# R303X.net
KiCad netlist of a schematic drawn in EAGLE
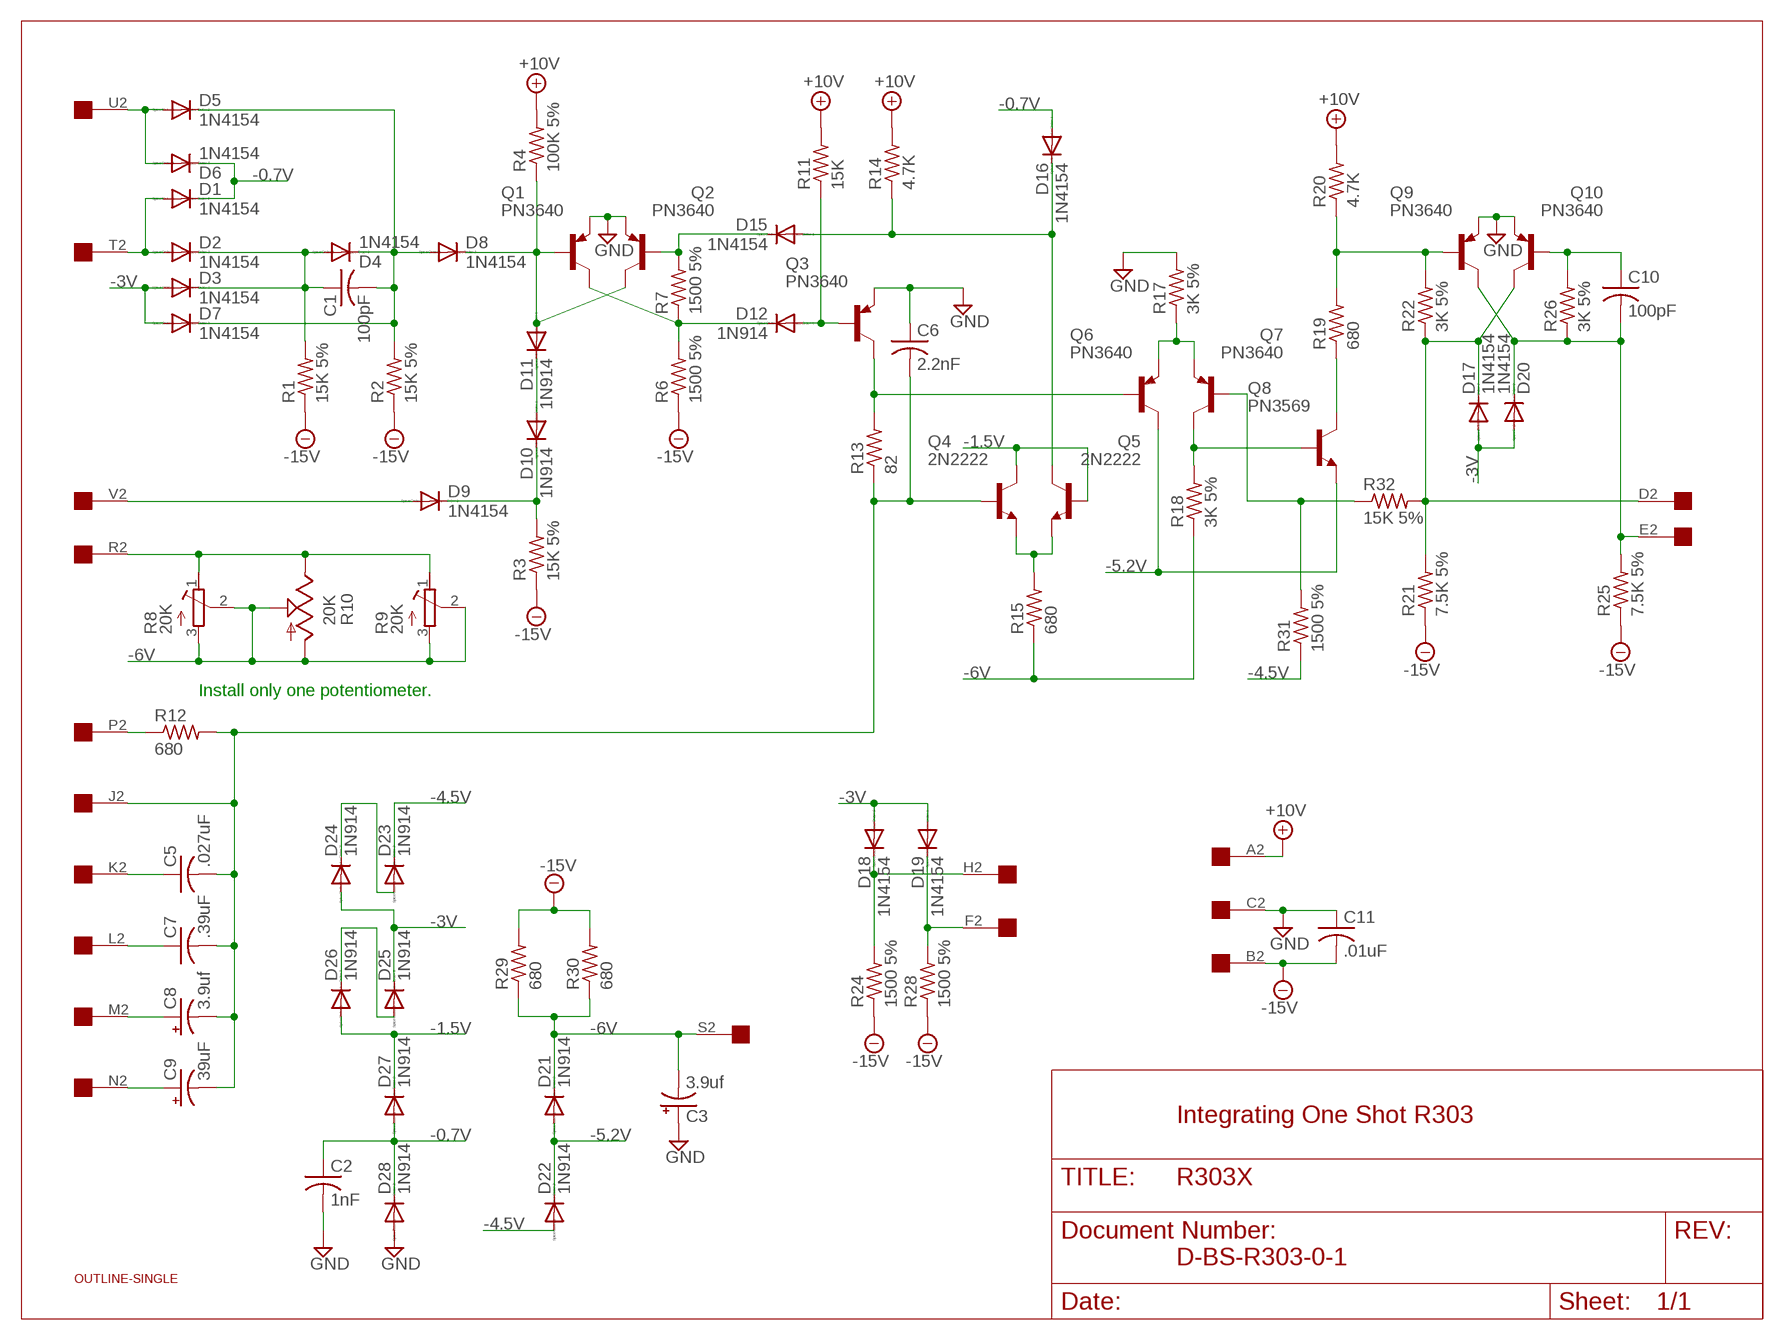
[diagram p0: schematic, sheet 1]

(export (version "E")
  (design (tool "Eeschema 10.0.6"))
  (components
    (comp (ref "C1")
      (value "100pF")
      (footprint "eagle-import:C075-032X103")
      (libsource (lib "eagle-import") (part "C-US075-032X103"))
    )
    (comp (ref "C2")
      (value "1nF")
      (footprint "eagle-import:C050-025X075")
      (libsource (lib "eagle-import") (part "C-US050-025X075"))
    )
    (comp (ref "C3")
      (value "3.9uf")
      (footprint "eagle-import:E12-4")
      (libsource (lib "eagle-import") (part "CPOL-USE12-4AXIAL"))
    )
    (comp (ref "C5")
      (value ".027uF")
      (footprint "eagle-import:C225-062X268")
      (libsource (lib "eagle-import") (part "C-US225-062X268"))
    )
    (comp (ref "C6")
      (value "2.2nF")
      (footprint "eagle-import:C050-025X075")
      (libsource (lib "eagle-import") (part "C-US050-025X075"))
    )
    (comp (ref "C7")
      (value ".39uF")
      (footprint "eagle-import:C325-137X374")
      (libsource (lib "eagle-import") (part "C-US325-137X374"))
    )
    (comp (ref "C8")
      (value "3.9uf")
      (footprint "eagle-import:E12-4")
      (libsource (lib "eagle-import") (part "CPOL-USE12-4AXIAL"))
    )
    (comp (ref "C9")
      (value "39uF")
      (footprint "eagle-import:E15-5")
      (libsource (lib "eagle-import") (part "CPOL-USE15-5AXIAL"))
    )
    (comp (ref "C10")
      (value "100pF")
      (footprint "eagle-import:C075-032X103")
      (libsource (lib "eagle-import") (part "C-US075-032X103"))
    )
    (comp (ref "C11")
      (value ".01uF")
      (footprint "eagle-import:C075-032X103")
      (libsource (lib "eagle-import") (part "C-US075-032X103"))
    )
    (comp (ref "D1")
      (value "1N4154")
      (footprint "eagle-import:DO35-10")
      (libsource (lib "eagle-import") (part "1N4148DO35-10"))
    )
    (comp (ref "D2")
      (value "1N4154")
      (footprint "eagle-import:DO35-10")
      (libsource (lib "eagle-import") (part "1N4148DO35-10"))
    )
    (comp (ref "D3")
      (value "1N4154")
      (footprint "eagle-import:DO35-10")
      (libsource (lib "eagle-import") (part "1N4148DO35-10"))
    )
    (comp (ref "D4")
      (value "1N4154")
      (footprint "eagle-import:DO35-10")
      (libsource (lib "eagle-import") (part "1N4148DO35-10"))
    )
    (comp (ref "D5")
      (value "1N4154")
      (footprint "eagle-import:DO35-10")
      (libsource (lib "eagle-import") (part "1N4148DO35-10"))
    )
    (comp (ref "D6")
      (value "1N4154")
      (footprint "eagle-import:DO35-10")
      (libsource (lib "eagle-import") (part "1N4148DO35-10"))
    )
    (comp (ref "D7")
      (value "1N4154")
      (footprint "eagle-import:DO35-10")
      (libsource (lib "eagle-import") (part "1N4148DO35-10"))
    )
    (comp (ref "D8")
      (value "1N4154")
      (footprint "eagle-import:DO35-10")
      (libsource (lib "eagle-import") (part "1N4148DO35-10"))
    )
    (comp (ref "D9")
      (value "1N4154")
      (footprint "eagle-import:DO35-10")
      (libsource (lib "eagle-import") (part "1N4148DO35-10"))
    )
    (comp (ref "D10")
      (value "1N914")
      (footprint "eagle-import:DO35-10")
      (libsource (lib "eagle-import") (part "1N4148DO35-10"))
    )
    (comp (ref "D11")
      (value "1N914")
      (footprint "eagle-import:DO35-10")
      (libsource (lib "eagle-import") (part "1N4148DO35-10"))
    )
    (comp (ref "D12")
      (value "1N914")
      (footprint "eagle-import:DO35-10")
      (libsource (lib "eagle-import") (part "1N4148DO35-10"))
    )
    (comp (ref "D15")
      (value "1N4154")
      (footprint "eagle-import:DO35-10")
      (libsource (lib "eagle-import") (part "1N4148DO35-10"))
    )
    (comp (ref "D16")
      (value "1N4154")
      (footprint "eagle-import:DO35-10")
      (libsource (lib "eagle-import") (part "1N4148DO35-10"))
    )
    (comp (ref "D17")
      (value "1N4154")
      (footprint "eagle-import:DO35-10")
      (libsource (lib "eagle-import") (part "1N4148DO35-10"))
    )
    (comp (ref "D18")
      (value "1N4154")
      (footprint "eagle-import:DO35-10")
      (libsource (lib "eagle-import") (part "1N4148DO35-10"))
    )
    (comp (ref "D19")
      (value "1N4154")
      (footprint "eagle-import:DO35-10")
      (libsource (lib "eagle-import") (part "1N4148DO35-10"))
    )
    (comp (ref "D20")
      (value "1N4154")
      (footprint "eagle-import:DO35-10")
      (libsource (lib "eagle-import") (part "1N4148DO35-10"))
    )
    (comp (ref "D21")
      (value "1N914")
      (footprint "eagle-import:DO35-10")
      (libsource (lib "eagle-import") (part "1N4148DO35-10"))
    )
    (comp (ref "D22")
      (value "1N914")
      (footprint "eagle-import:DO35-10")
      (libsource (lib "eagle-import") (part "1N4148DO35-10"))
    )
    (comp (ref "D23")
      (value "1N914")
      (footprint "eagle-import:DO35-10")
      (libsource (lib "eagle-import") (part "1N4148DO35-10"))
    )
    (comp (ref "D24")
      (value "1N914")
      (footprint "eagle-import:DO35-10")
      (libsource (lib "eagle-import") (part "1N4148DO35-10"))
    )
    (comp (ref "D25")
      (value "1N914")
      (footprint "eagle-import:DO35-10")
      (libsource (lib "eagle-import") (part "1N4148DO35-10"))
    )
    (comp (ref "D26")
      (value "1N914")
      (footprint "eagle-import:DO35-10")
      (libsource (lib "eagle-import") (part "1N4148DO35-10"))
    )
    (comp (ref "D27")
      (value "1N914")
      (footprint "eagle-import:DO35-10")
      (libsource (lib "eagle-import") (part "1N4148DO35-10"))
    )
    (comp (ref "D28")
      (value "1N914")
      (footprint "eagle-import:DO35-10")
      (libsource (lib "eagle-import") (part "1N4148DO35-10"))
    )
    (comp (ref "Q1")
      (value "PN3640")
      (footprint "eagle-import:TO39")
      (libsource (lib "eagle-import") (part "2N2904"))
    )
    (comp (ref "Q2")
      (value "PN3640")
      (footprint "eagle-import:TO39")
      (libsource (lib "eagle-import") (part "2N2904"))
    )
    (comp (ref "Q3")
      (value "PN3640")
      (footprint "eagle-import:TO39")
      (libsource (lib "eagle-import") (part "2N2904"))
    )
    (comp (ref "Q4")
      (value "2N2222")
      (footprint "eagle-import:TO5")
      (libsource (lib "eagle-import") (part "2N2102"))
    )
    (comp (ref "Q5")
      (value "2N2222")
      (footprint "eagle-import:TO5")
      (libsource (lib "eagle-import") (part "2N2102"))
    )
    (comp (ref "Q6")
      (value "PN3640")
      (footprint "eagle-import:TO39")
      (libsource (lib "eagle-import") (part "2N2904"))
    )
    (comp (ref "Q7")
      (value "PN3640")
      (footprint "eagle-import:TO39")
      (libsource (lib "eagle-import") (part "2N2904"))
    )
    (comp (ref "Q8")
      (value "PN3569")
      (footprint "eagle-import:TO5")
      (libsource (lib "eagle-import") (part "2N2102"))
    )
    (comp (ref "Q9")
      (value "PN3640")
      (footprint "eagle-import:TO39")
      (libsource (lib "eagle-import") (part "2N2904"))
    )
    (comp (ref "Q10")
      (value "PN3640")
      (footprint "eagle-import:TO39")
      (libsource (lib "eagle-import") (part "2N2904"))
    )
    (comp (ref "R1")
      (value "15K 5%")
      (footprint "eagle-import:0207_10")
      (libsource (lib "eagle-import") (part "R-US_0207/10"))
    )
    (comp (ref "R2")
      (value "15K 5%")
      (footprint "eagle-import:0207_10")
      (libsource (lib "eagle-import") (part "R-US_0207/10"))
    )
    (comp (ref "R3")
      (value "15K 5%")
      (footprint "eagle-import:0207_10")
      (libsource (lib "eagle-import") (part "R-US_0207/10"))
    )
    (comp (ref "R4")
      (value "100K 5%")
      (footprint "eagle-import:0207_10")
      (libsource (lib "eagle-import") (part "R-US_0207/10"))
    )
    (comp (ref "R6")
      (value "1500 5%")
      (footprint "eagle-import:0207_10")
      (libsource (lib "eagle-import") (part "R-US_0207/10"))
    )
    (comp (ref "R7")
      (value "1500 5%")
      (footprint "eagle-import:0207_10")
      (libsource (lib "eagle-import") (part "R-US_0207/10"))
    )
    (comp (ref "R8")
      (value "20K")
      (footprint "eagle-import:RTRIM43P")
      (libsource (lib "eagle-import") (part "R-TRIMM43P"))
    )
    (comp (ref "R9")
      (value "20K")
      (footprint "eagle-import:3006Y")
      (libsource (lib "eagle-import") (part "275P"))
    )
    (comp (ref "R10")
      (value "20K")
      (footprint "eagle-import:B25P")
      (libsource (lib "eagle-import") (part "TRIM_US-B25P"))
    )
    (comp (ref "R11")
      (value "15K")
      (footprint "eagle-import:0207_10")
      (libsource (lib "eagle-import") (part "R-US_0207/10"))
    )
    (comp (ref "R12")
      (value "680")
      (footprint "eagle-import:0207_10")
      (libsource (lib "eagle-import") (part "R-US_0207/10"))
    )
    (comp (ref "R13")
      (value "82")
      (footprint "eagle-import:0207_10")
      (libsource (lib "eagle-import") (part "R-US_0207/10"))
    )
    (comp (ref "R14")
      (value "4.7K")
      (footprint "eagle-import:0207_10")
      (libsource (lib "eagle-import") (part "R-US_0207/10"))
    )
    (comp (ref "R15")
      (value "680")
      (footprint "eagle-import:0207_10")
      (libsource (lib "eagle-import") (part "R-US_0207/10"))
    )
    (comp (ref "R17")
      (value "3K 5%")
      (footprint "eagle-import:0207_10")
      (libsource (lib "eagle-import") (part "R-US_0207/10"))
    )
    (comp (ref "R18")
      (value "3K 5%")
      (footprint "eagle-import:0207_10")
      (libsource (lib "eagle-import") (part "R-US_0207/10"))
    )
    (comp (ref "R19")
      (value "680")
      (footprint "eagle-import:0207_10")
      (libsource (lib "eagle-import") (part "R-US_0207/10"))
    )
    (comp (ref "R20")
      (value "4.7K")
      (footprint "eagle-import:0207_10")
      (libsource (lib "eagle-import") (part "R-US_0207/10"))
    )
    (comp (ref "R21")
      (value "7.5K 5%")
      (footprint "eagle-import:0207_10")
      (libsource (lib "eagle-import") (part "R-US_0207/10"))
    )
    (comp (ref "R22")
      (value "3K 5%")
      (footprint "eagle-import:0207_10")
      (libsource (lib "eagle-import") (part "R-US_0207/10"))
    )
    (comp (ref "R24")
      (value "1500 5%")
      (footprint "eagle-import:0207_10")
      (libsource (lib "eagle-import") (part "R-US_0207/10"))
    )
    (comp (ref "R25")
      (value "7.5K 5%")
      (footprint "eagle-import:0207_10")
      (libsource (lib "eagle-import") (part "R-US_0207/10"))
    )
    (comp (ref "R26")
      (value "3K 5%")
      (footprint "eagle-import:0207_10")
      (libsource (lib "eagle-import") (part "R-US_0207/10"))
    )
    (comp (ref "R28")
      (value "1500 5%")
      (footprint "eagle-import:0207_10")
      (libsource (lib "eagle-import") (part "R-US_0207/10"))
    )
    (comp (ref "R29")
      (value "680")
      (footprint "eagle-import:0207_10")
      (libsource (lib "eagle-import") (part "R-US_0207/10"))
    )
    (comp (ref "R30")
      (value "680")
      (footprint "eagle-import:0207_10")
      (libsource (lib "eagle-import") (part "R-US_0207/10"))
    )
    (comp (ref "R31")
      (value "1500 5%")
      (footprint "eagle-import:0207_10")
      (libsource (lib "eagle-import") (part "R-US_0207/10"))
    )
    (comp (ref "R32")
      (value "15K 5%")
      (footprint "eagle-import:0207_10")
      (libsource (lib "eagle-import") (part "R-US_0207/10"))
    )
    (comp (ref "U$1")
      (value "OUTLINE-SINGLE")
      (footprint "eagle-import:SINGLE")
      (libsource (lib "eagle-import") (part "OUTLINE-SINGLE"))
    )
    (comp (ref "U$2")
      (value "EDGE-1")
      (footprint "eagle-import:EDGE-CON1")
      (libsource (lib "eagle-import") (part "EDGE-1"))
    )
  )
  (nets
    (net (code "1") (name "+10V") (class "Default")
      (node (ref "R11") (pin "2") (pinfunction "2_2") (pintype "passive"))
      (node (ref "R14") (pin "2") (pinfunction "2_2") (pintype "passive"))
      (node (ref "R20") (pin "2") (pinfunction "2_2") (pintype "passive"))
      (node (ref "R4") (pin "2") (pinfunction "2_2") (pintype "passive"))
      (node (ref "U$2") (pin "A2") (pinfunction "1_A2") (pintype "bidirectional"))
    )
    (net (code "2") (name "-15V") (class "Default")
      (node (ref "C11") (pin "2") (pinfunction "2_2") (pintype "passive"))
      (node (ref "R1") (pin "1") (pinfunction "1_1") (pintype "passive"))
      (node (ref "R2") (pin "1") (pinfunction "1_1") (pintype "passive"))
      (node (ref "R21") (pin "1") (pinfunction "1_1") (pintype "passive"))
      (node (ref "R24") (pin "1") (pinfunction "1_1") (pintype "passive"))
      (node (ref "R25") (pin "1") (pinfunction "1_1") (pintype "passive"))
      (node (ref "R28") (pin "1") (pinfunction "1_1") (pintype "passive"))
      (node (ref "R29") (pin "2") (pinfunction "2_2") (pintype "passive"))
      (node (ref "R3") (pin "1") (pinfunction "1_1") (pintype "passive"))
      (node (ref "R30") (pin "2") (pinfunction "2_2") (pintype "passive"))
      (node (ref "R6") (pin "1") (pinfunction "1_1") (pintype "passive"))
      (node (ref "U$2") (pin "B2") (pinfunction "1_B2") (pintype "bidirectional"))
    )
    (net (code "3") (name "/-0.7V") (class "Default")
      (node (ref "C2") (pin "1") (pinfunction "1_1") (pintype "passive"))
      (node (ref "D1") (pin "C") (pinfunction "C_C") (pintype "passive"))
      (node (ref "D16") (pin "A") (pinfunction "A_A") (pintype "passive"))
      (node (ref "D27") (pin "A") (pinfunction "A_A") (pintype "passive"))
      (node (ref "D28") (pin "C") (pinfunction "C_C") (pintype "passive"))
      (node (ref "D6") (pin "C") (pinfunction "C_C") (pintype "passive"))
    )
    (net (code "4") (name "/-1.5V") (class "Default")
      (node (ref "D26") (pin "A") (pinfunction "A_A") (pintype "passive"))
      (node (ref "D27") (pin "C") (pinfunction "C_C") (pintype "passive"))
      (node (ref "Q4") (pin "3") (pinfunction "C_3") (pintype "passive"))
      (node (ref "Q5") (pin "2") (pinfunction "B_2") (pintype "passive"))
    )
    (net (code "5") (name "/-3V") (class "Default")
      (node (ref "D17") (pin "A") (pinfunction "A_A") (pintype "passive"))
      (node (ref "D18") (pin "A") (pinfunction "A_A") (pintype "passive"))
      (node (ref "D19") (pin "A") (pinfunction "A_A") (pintype "passive"))
      (node (ref "D20") (pin "A") (pinfunction "A_A") (pintype "passive"))
      (node (ref "D24") (pin "A") (pinfunction "A_A") (pintype "passive"))
      (node (ref "D25") (pin "C") (pinfunction "C_C") (pintype "passive"))
      (node (ref "D3") (pin "A") (pinfunction "A_A") (pintype "passive"))
      (node (ref "D7") (pin "A") (pinfunction "A_A") (pintype "passive"))
    )
    (net (code "6") (name "/-4.5V") (class "Default")
      (node (ref "D22") (pin "A") (pinfunction "A_A") (pintype "passive"))
      (node (ref "D23") (pin "C") (pinfunction "C_C") (pintype "passive"))
      (node (ref "R31") (pin "1") (pinfunction "1_1") (pintype "passive"))
    )
    (net (code "7") (name "/-5.2V") (class "Default")
      (node (ref "D21") (pin "A") (pinfunction "A_A") (pintype "passive"))
      (node (ref "D22") (pin "C") (pinfunction "C_C") (pintype "passive"))
      (node (ref "Q6") (pin "3") (pinfunction "C_3") (pintype "passive"))
      (node (ref "Q8") (pin "1") (pinfunction "E_1") (pintype "passive"))
    )
    (net (code "8") (name "/-6V") (class "Default")
      (node (ref "C3") (pin "-") (pinfunction "-_-") (pintype "passive"))
      (node (ref "D21") (pin "C") (pinfunction "C_C") (pintype "passive"))
      (node (ref "R10") (pin "A") (pinfunction "A_A") (pintype "passive"))
      (node (ref "R10") (pin "S") (pinfunction "S_S") (pintype "passive"))
      (node (ref "R15") (pin "1") (pinfunction "1_1") (pintype "passive"))
      (node (ref "R18") (pin "1") (pinfunction "1_1") (pintype "passive"))
      (node (ref "R29") (pin "1") (pinfunction "1_1") (pintype "passive"))
      (node (ref "R30") (pin "1") (pinfunction "1_1") (pintype "passive"))
      (node (ref "R8") (pin "2") (pinfunction "S_2") (pintype "passive"))
      (node (ref "R8") (pin "3") (pinfunction "A_3") (pintype "passive"))
      (node (ref "R9") (pin "2") (pinfunction "S_2") (pintype "passive"))
      (node (ref "R9") (pin "3") (pinfunction "E_3") (pintype "passive"))
      (node (ref "U$2") (pin "S2") (pinfunction "1_S2") (pintype "bidirectional"))
    )
    (net (code "9") (name "GND") (class "Default")
      (node (ref "C11") (pin "1") (pinfunction "1_1") (pintype "passive"))
      (node (ref "C2") (pin "2") (pinfunction "2_2") (pintype "passive"))
      (node (ref "C3") (pin "+") (pinfunction "+_+") (pintype "passive"))
      (node (ref "C6") (pin "1") (pinfunction "1_1") (pintype "passive"))
      (node (ref "D28") (pin "A") (pinfunction "A_A") (pintype "passive"))
      (node (ref "Q1") (pin "1") (pinfunction "E_1") (pintype "passive"))
      (node (ref "Q10") (pin "1") (pinfunction "E_1") (pintype "passive"))
      (node (ref "Q2") (pin "1") (pinfunction "E_1") (pintype "passive"))
      (node (ref "Q3") (pin "1") (pinfunction "E_1") (pintype "passive"))
      (node (ref "Q9") (pin "1") (pinfunction "E_1") (pintype "passive"))
      (node (ref "R17") (pin "2") (pinfunction "2_2") (pintype "passive"))
      (node (ref "U$2") (pin "C2") (pinfunction "1_C2") (pintype "bidirectional"))
    )
    (net (code "10") (name "Net-(C1-Pad1)") (class "Default")
      (node (ref "C1") (pin "1") (pinfunction "1_1") (pintype "passive"))
      (node (ref "D2") (pin "C") (pinfunction "C_C") (pintype "passive"))
      (node (ref "D3") (pin "C") (pinfunction "C_C") (pintype "passive"))
      (node (ref "D4") (pin "A") (pinfunction "A_A") (pintype "passive"))
      (node (ref "R1") (pin "2") (pinfunction "2_2") (pintype "passive"))
    )
    (net (code "11") (name "Net-(C1-Pad2)") (class "Default")
      (node (ref "C1") (pin "2") (pinfunction "2_2") (pintype "passive"))
      (node (ref "D4") (pin "C") (pinfunction "C_C") (pintype "passive"))
      (node (ref "D5") (pin "C") (pinfunction "C_C") (pintype "passive"))
      (node (ref "D7") (pin "C") (pinfunction "C_C") (pintype "passive"))
      (node (ref "D8") (pin "A") (pinfunction "A_A") (pintype "passive"))
      (node (ref "R2") (pin "2") (pinfunction "2_2") (pintype "passive"))
    )
    (net (code "12") (name "Net-(D10-PadA)") (class "Default")
      (node (ref "D10") (pin "A") (pinfunction "A_A") (pintype "passive"))
      (node (ref "D11") (pin "C") (pinfunction "C_C") (pintype "passive"))
    )
    (net (code "13") (name "Net-(D10-PadC)") (class "Default")
      (node (ref "D10") (pin "C") (pinfunction "C_C") (pintype "passive"))
      (node (ref "D9") (pin "C") (pinfunction "C_C") (pintype "passive"))
      (node (ref "R3") (pin "2") (pinfunction "2_2") (pintype "passive"))
    )
    (net (code "14") (name "Net-(D23-PadA)") (class "Default")
      (node (ref "D23") (pin "A") (pinfunction "A_A") (pintype "passive"))
      (node (ref "D24") (pin "C") (pinfunction "C_C") (pintype "passive"))
    )
    (net (code "15") (name "Net-(D25-PadA)") (class "Default")
      (node (ref "D25") (pin "A") (pinfunction "A_A") (pintype "passive"))
      (node (ref "D26") (pin "C") (pinfunction "C_C") (pintype "passive"))
    )
    (net (code "16") (name "Net-(Q1-B)") (class "Default")
      (node (ref "D11") (pin "A") (pinfunction "A_A") (pintype "passive"))
      (node (ref "D8") (pin "C") (pinfunction "C_C") (pintype "passive"))
      (node (ref "Q1") (pin "2") (pinfunction "B_2") (pintype "passive"))
      (node (ref "Q2") (pin "3") (pinfunction "C_3") (pintype "passive"))
      (node (ref "R4") (pin "1") (pinfunction "1_1") (pintype "passive"))
    )
    (net (code "17") (name "Net-(Q1-C)") (class "Default")
      (node (ref "D12") (pin "C") (pinfunction "C_C") (pintype "passive"))
      (node (ref "Q1") (pin "3") (pinfunction "C_3") (pintype "passive"))
      (node (ref "R6") (pin "2") (pinfunction "2_2") (pintype "passive"))
      (node (ref "R7") (pin "1") (pinfunction "1_1") (pintype "passive"))
    )
    (net (code "18") (name "Net-(Q2-B)") (class "Default")
      (node (ref "D15") (pin "C") (pinfunction "C_C") (pintype "passive"))
      (node (ref "Q2") (pin "2") (pinfunction "B_2") (pintype "passive"))
      (node (ref "R7") (pin "2") (pinfunction "2_2") (pintype "passive"))
    )
    (net (code "19") (name "Net-(Q3-B)") (class "Default")
      (node (ref "D12") (pin "A") (pinfunction "A_A") (pintype "passive"))
      (node (ref "Q3") (pin "2") (pinfunction "B_2") (pintype "passive"))
      (node (ref "R11") (pin "1") (pinfunction "1_1") (pintype "passive"))
    )
    (net (code "20") (name "Net-(Q3-C)") (class "Default")
      (node (ref "Q3") (pin "3") (pinfunction "C_3") (pintype "passive"))
      (node (ref "Q6") (pin "2") (pinfunction "B_2") (pintype "passive"))
      (node (ref "R13") (pin "2") (pinfunction "2_2") (pintype "passive"))
    )
    (net (code "21") (name "Net-(Q4-B)") (class "Default")
      (node (ref "C5") (pin "2") (pinfunction "2_2") (pintype "passive"))
      (node (ref "C6") (pin "2") (pinfunction "2_2") (pintype "passive"))
      (node (ref "C7") (pin "2") (pinfunction "2_2") (pintype "passive"))
      (node (ref "C8") (pin "-") (pinfunction "-_-") (pintype "passive"))
      (node (ref "C9") (pin "-") (pinfunction "-_-") (pintype "passive"))
      (node (ref "Q4") (pin "2") (pinfunction "B_2") (pintype "passive"))
      (node (ref "R12") (pin "2") (pinfunction "2_2") (pintype "passive"))
      (node (ref "R13") (pin "1") (pinfunction "1_1") (pintype "passive"))
      (node (ref "U$2") (pin "J2") (pinfunction "1_J2") (pintype "bidirectional"))
    )
    (net (code "22") (name "Net-(Q4-E)") (class "Default")
      (node (ref "Q4") (pin "1") (pinfunction "E_1") (pintype "passive"))
      (node (ref "Q5") (pin "1") (pinfunction "E_1") (pintype "passive"))
      (node (ref "R15") (pin "2") (pinfunction "2_2") (pintype "passive"))
    )
    (net (code "23") (name "Net-(Q5-C)") (class "Default")
      (node (ref "D15") (pin "A") (pinfunction "A_A") (pintype "passive"))
      (node (ref "D16") (pin "C") (pinfunction "C_C") (pintype "passive"))
      (node (ref "Q5") (pin "3") (pinfunction "C_3") (pintype "passive"))
      (node (ref "R14") (pin "1") (pinfunction "1_1") (pintype "passive"))
    )
    (net (code "24") (name "Net-(Q6-E)") (class "Default")
      (node (ref "Q6") (pin "1") (pinfunction "E_1") (pintype "passive"))
      (node (ref "Q7") (pin "1") (pinfunction "E_1") (pintype "passive"))
      (node (ref "R17") (pin "1") (pinfunction "1_1") (pintype "passive"))
    )
    (net (code "25") (name "Net-(Q7-B)") (class "Default")
      (node (ref "Q7") (pin "2") (pinfunction "B_2") (pintype "passive"))
      (node (ref "R31") (pin "2") (pinfunction "2_2") (pintype "passive"))
      (node (ref "R32") (pin "1") (pinfunction "1_1") (pintype "passive"))
    )
    (net (code "26") (name "Net-(Q7-C)") (class "Default")
      (node (ref "Q7") (pin "3") (pinfunction "C_3") (pintype "passive"))
      (node (ref "Q8") (pin "2") (pinfunction "B_2") (pintype "passive"))
      (node (ref "R18") (pin "2") (pinfunction "2_2") (pintype "passive"))
    )
    (net (code "27") (name "Net-(Q8-C)") (class "Default")
      (node (ref "Q8") (pin "3") (pinfunction "C_3") (pintype "passive"))
      (node (ref "R19") (pin "1") (pinfunction "1_1") (pintype "passive"))
    )
    (net (code "28") (name "Net-(Q9-B)") (class "Default")
      (node (ref "Q9") (pin "2") (pinfunction "B_2") (pintype "passive"))
      (node (ref "R19") (pin "2") (pinfunction "2_2") (pintype "passive"))
      (node (ref "R20") (pin "1") (pinfunction "1_1") (pintype "passive"))
      (node (ref "R22") (pin "2") (pinfunction "2_2") (pintype "passive"))
    )
    (net (code "29") (name "Net-(Q9-C)") (class "Default")
      (node (ref "C10") (pin "2") (pinfunction "2_2") (pintype "passive"))
      (node (ref "D20") (pin "C") (pinfunction "C_C") (pintype "passive"))
      (node (ref "Q9") (pin "3") (pinfunction "C_3") (pintype "passive"))
      (node (ref "R25") (pin "2") (pinfunction "2_2") (pintype "passive"))
      (node (ref "R26") (pin "1") (pinfunction "1_1") (pintype "passive"))
      (node (ref "U$2") (pin "E2") (pinfunction "1_E2") (pintype "bidirectional"))
    )
    (net (code "30") (name "Net-(Q10-B)") (class "Default")
      (node (ref "C10") (pin "1") (pinfunction "1_1") (pintype "passive"))
      (node (ref "Q10") (pin "2") (pinfunction "B_2") (pintype "passive"))
      (node (ref "R26") (pin "2") (pinfunction "2_2") (pintype "passive"))
    )
    (net (code "31") (name "Net-(Q10-C)") (class "Default")
      (node (ref "D17") (pin "C") (pinfunction "C_C") (pintype "passive"))
      (node (ref "Q10") (pin "3") (pinfunction "C_3") (pintype "passive"))
      (node (ref "R21") (pin "2") (pinfunction "2_2") (pintype "passive"))
      (node (ref "R22") (pin "1") (pinfunction "1_1") (pintype "passive"))
      (node (ref "R32") (pin "2") (pinfunction "2_2") (pintype "passive"))
      (node (ref "U$2") (pin "D2") (pinfunction "1_D2") (pintype "bidirectional"))
    )
    (net (code "32") (name "Net-(R8-E)") (class "Default")
      (node (ref "R10") (pin "E") (pinfunction "E_E") (pintype "passive"))
      (node (ref "R8") (pin "1") (pinfunction "E_1") (pintype "passive"))
      (node (ref "R9") (pin "1") (pinfunction "A_1") (pintype "passive"))
      (node (ref "U$2") (pin "R2") (pinfunction "1_R2") (pintype "bidirectional"))
    )
    (net (code "33") (name "Net-(U$2F-1)") (class "Default")
      (node (ref "D19") (pin "C") (pinfunction "C_C") (pintype "passive"))
      (node (ref "R28") (pin "2") (pinfunction "2_2") (pintype "passive"))
      (node (ref "U$2") (pin "F2") (pinfunction "1_F2") (pintype "bidirectional"))
    )
    (net (code "34") (name "Net-(U$2G-1)") (class "Default")
      (node (ref "D18") (pin "C") (pinfunction "C_C") (pintype "passive"))
      (node (ref "R24") (pin "2") (pinfunction "2_2") (pintype "passive"))
      (node (ref "U$2") (pin "H2") (pinfunction "1_H2") (pintype "bidirectional"))
    )
    (net (code "35") (name "Net-(U$2I-1)") (class "Default")
      (node (ref "C5") (pin "1") (pinfunction "1_1") (pintype "passive"))
      (node (ref "U$2") (pin "K2") (pinfunction "1_K2") (pintype "bidirectional"))
    )
    (net (code "36") (name "Net-(U$2J-1)") (class "Default")
      (node (ref "C7") (pin "1") (pinfunction "1_1") (pintype "passive"))
      (node (ref "U$2") (pin "L2") (pinfunction "1_L2") (pintype "bidirectional"))
    )
    (net (code "37") (name "Net-(U$2K-1)") (class "Default")
      (node (ref "C8") (pin "+") (pinfunction "+_+") (pintype "passive"))
      (node (ref "U$2") (pin "M2") (pinfunction "1_M2") (pintype "bidirectional"))
    )
    (net (code "38") (name "Net-(U$2L-1)") (class "Default")
      (node (ref "C9") (pin "+") (pinfunction "+_+") (pintype "passive"))
      (node (ref "U$2") (pin "N2") (pinfunction "1_N2") (pintype "bidirectional"))
    )
    (net (code "39") (name "Net-(U$2M-1)") (class "Default")
      (node (ref "R12") (pin "1") (pinfunction "1_1") (pintype "passive"))
      (node (ref "U$2") (pin "P2") (pinfunction "1_P2") (pintype "bidirectional"))
    )
    (net (code "40") (name "Net-(U$2P-1)") (class "Default")
      (node (ref "D1") (pin "A") (pinfunction "A_A") (pintype "passive"))
      (node (ref "D2") (pin "A") (pinfunction "A_A") (pintype "passive"))
      (node (ref "U$2") (pin "T2") (pinfunction "1_T2") (pintype "bidirectional"))
    )
    (net (code "41") (name "Net-(U$2Q-1)") (class "Default")
      (node (ref "D5") (pin "A") (pinfunction "A_A") (pintype "passive"))
      (node (ref "D6") (pin "A") (pinfunction "A_A") (pintype "passive"))
      (node (ref "U$2") (pin "U2") (pinfunction "1_U2") (pintype "bidirectional"))
    )
    (net (code "42") (name "Net-(U$2R-1)") (class "Default")
      (node (ref "D9") (pin "A") (pinfunction "A_A") (pintype "passive"))
      (node (ref "U$2") (pin "V2") (pinfunction "1_V2") (pintype "bidirectional"))
    )
  )
)
